# 07-SNESDRONE_Direct_IO_CART.net
KiCad netlist of a schematic drawn in Altium Designer
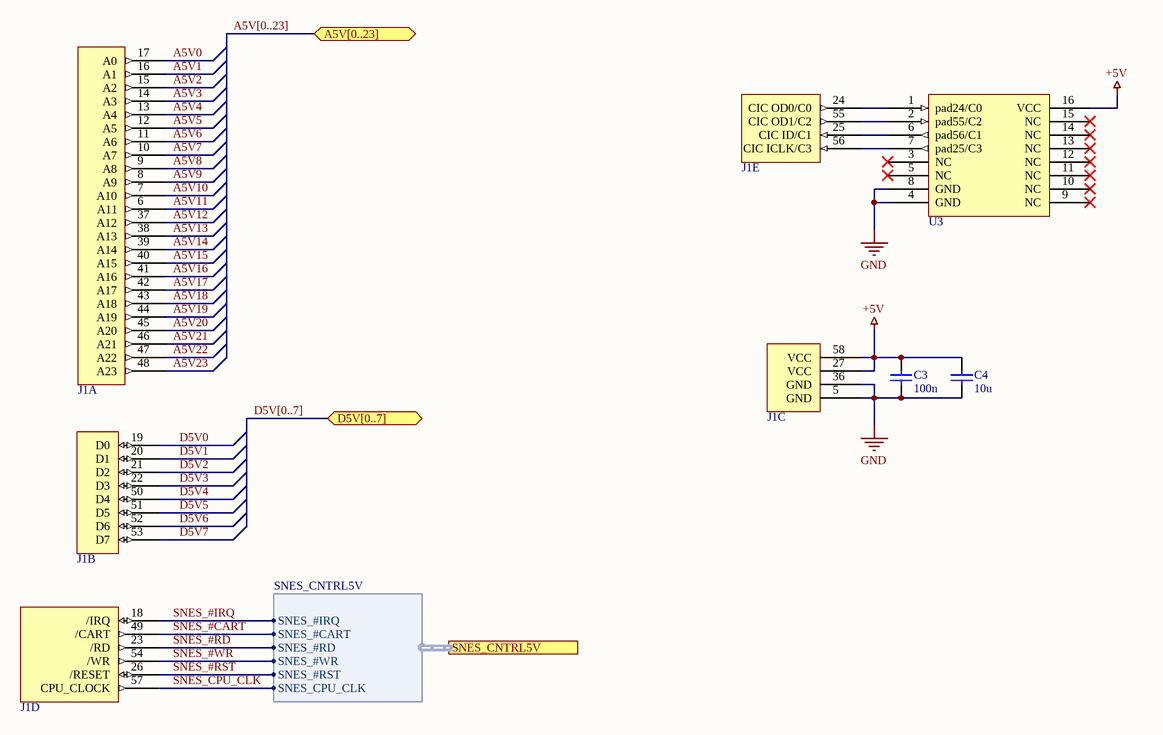
[diagram p0: 07-SNESDRONE_Direct_IO_CART.SchDoc]

(export (version "E")
  (design (tool "Eeschema 10.0.6"))
  (components
    (comp (ref "C3")
      (value "100n")
      (footprint "cap_0603")
      (description "Capacitor")
      (fields (field (name "Comment") "cap_0603"))
      (libsource (lib "mycomponents") (part "cap_0603"))
    )
    (comp (ref "C4")
      (value "10u")
      (footprint "cap_0603")
      (description "Capacitor")
      (fields (field (name "Comment") "cap_0603"))
      (libsource (lib "mycomponents") (part "cap_0603"))
    )
    (comp (ref "J1")
      (value "SNES Cartridge Connector")
      (footprint "SNES Cartridge Connector")
      (libsource (lib "") (part "SNES Cartridge Connector_1"))
    )
    (comp (ref "U3")
      (value "IC_D411A")
      (footprint "DIP16")
      (description "SNES CIC Chip")
      (libsource (lib "mycomponents") (part "IC_D411A"))
    )
  )
  (nets
    (net (code "2") (name "+5V") (class "Default")
      (node (ref "C3") (pin "2") (pinfunction "2_2") (pintype "passive"))
      (node (ref "C4") (pin "2") (pinfunction "2_2") (pintype "passive"))
      (node (ref "J1") (pin "27") (pinfunction "VCC_27") (pintype "power_in"))
      (node (ref "J1") (pin "58") (pinfunction "VCC_58") (pintype "power_in"))
      (node (ref "U3") (pin "16") (pinfunction "VCC_16") (pintype "power_in"))
    )
    (net (code "3") (name "/A5V0") (class "Default")
      (node (ref "J1") (pin "17") (pinfunction "A0_17") (pintype "output"))
    )
    (net (code "4") (name "/A5V1") (class "Default")
      (node (ref "J1") (pin "16") (pinfunction "A1_16") (pintype "output"))
    )
    (net (code "5") (name "/A5V2") (class "Default")
      (node (ref "J1") (pin "15") (pinfunction "A2_15") (pintype "output"))
    )
    (net (code "6") (name "/A5V3") (class "Default")
      (node (ref "J1") (pin "14") (pinfunction "A3_14") (pintype "output"))
    )
    (net (code "7") (name "/A5V4") (class "Default")
      (node (ref "J1") (pin "13") (pinfunction "A4_13") (pintype "output"))
    )
    (net (code "8") (name "/A5V5") (class "Default")
      (node (ref "J1") (pin "12") (pinfunction "A5_12") (pintype "output"))
    )
    (net (code "9") (name "/A5V6") (class "Default")
      (node (ref "J1") (pin "11") (pinfunction "A6_11") (pintype "output"))
    )
    (net (code "10") (name "/A5V7") (class "Default")
      (node (ref "J1") (pin "10") (pinfunction "A7_10") (pintype "output"))
    )
    (net (code "11") (name "/A5V8") (class "Default")
      (node (ref "J1") (pin "9") (pinfunction "A8_9") (pintype "output"))
    )
    (net (code "12") (name "/A5V9") (class "Default")
      (node (ref "J1") (pin "8") (pinfunction "A9_8") (pintype "output"))
    )
    (net (code "13") (name "/A5V10") (class "Default")
      (node (ref "J1") (pin "7") (pinfunction "A10_7") (pintype "output"))
    )
    (net (code "14") (name "/A5V11") (class "Default")
      (node (ref "J1") (pin "6") (pinfunction "A11_6") (pintype "output"))
    )
    (net (code "15") (name "/A5V12") (class "Default")
      (node (ref "J1") (pin "37") (pinfunction "A12_37") (pintype "output"))
    )
    (net (code "16") (name "/A5V13") (class "Default")
      (node (ref "J1") (pin "38") (pinfunction "A13_38") (pintype "output"))
    )
    (net (code "17") (name "/A5V14") (class "Default")
      (node (ref "J1") (pin "39") (pinfunction "A14_39") (pintype "output"))
    )
    (net (code "18") (name "/A5V15") (class "Default")
      (node (ref "J1") (pin "40") (pinfunction "A15_40") (pintype "output"))
    )
    (net (code "19") (name "/A5V16") (class "Default")
      (node (ref "J1") (pin "41") (pinfunction "A16_41") (pintype "output"))
    )
    (net (code "20") (name "/A5V17") (class "Default")
      (node (ref "J1") (pin "42") (pinfunction "A17_42") (pintype "output"))
    )
    (net (code "21") (name "/A5V18") (class "Default")
      (node (ref "J1") (pin "43") (pinfunction "A18_43") (pintype "output"))
    )
    (net (code "22") (name "/A5V19") (class "Default")
      (node (ref "J1") (pin "44") (pinfunction "A19_44") (pintype "output"))
    )
    (net (code "23") (name "/A5V20") (class "Default")
      (node (ref "J1") (pin "45") (pinfunction "A20_45") (pintype "output"))
    )
    (net (code "24") (name "/A5V21") (class "Default")
      (node (ref "J1") (pin "46") (pinfunction "A21_46") (pintype "output"))
    )
    (net (code "25") (name "/A5V22") (class "Default")
      (node (ref "J1") (pin "47") (pinfunction "A22_47") (pintype "output"))
    )
    (net (code "26") (name "/A5V23") (class "Default")
      (node (ref "J1") (pin "48") (pinfunction "A23_48") (pintype "output"))
    )
    (net (code "28") (name "/D5V0") (class "Default")
      (node (ref "J1") (pin "19") (pinfunction "D0_19") (pintype "bidirectional"))
    )
    (net (code "29") (name "/D5V1") (class "Default")
      (node (ref "J1") (pin "20") (pinfunction "D1_20") (pintype "bidirectional"))
    )
    (net (code "30") (name "/D5V2") (class "Default")
      (node (ref "J1") (pin "21") (pinfunction "D2_21") (pintype "bidirectional"))
    )
    (net (code "31") (name "/D5V3") (class "Default")
      (node (ref "J1") (pin "22") (pinfunction "D3_22") (pintype "bidirectional"))
    )
    (net (code "32") (name "/D5V4") (class "Default")
      (node (ref "J1") (pin "50") (pinfunction "D4_50") (pintype "bidirectional"))
    )
    (net (code "33") (name "/D5V5") (class "Default")
      (node (ref "J1") (pin "51") (pinfunction "D5_51") (pintype "bidirectional"))
    )
    (net (code "34") (name "/D5V6") (class "Default")
      (node (ref "J1") (pin "52") (pinfunction "D6_52") (pintype "bidirectional"))
    )
    (net (code "35") (name "/D5V7") (class "Default")
      (node (ref "J1") (pin "53") (pinfunction "D7_53") (pintype "bidirectional"))
    )
    (net (code "37") (name "/SNES_#CART") (class "Default")
      (node (ref "J1") (pin "49") (pinfunction "/CART_49") (pintype "output"))
    )
    (net (code "38") (name "/SNES_#IRQ") (class "Default")
      (node (ref "J1") (pin "18") (pinfunction "/IRQ_18") (pintype "bidirectional"))
    )
    (net (code "39") (name "/SNES_#RD") (class "Default")
      (node (ref "J1") (pin "23") (pinfunction "/RD_23") (pintype "output"))
    )
    (net (code "40") (name "/SNES_#RST") (class "Default")
      (node (ref "J1") (pin "26") (pinfunction "/RESET_26") (pintype "bidirectional"))
    )
    (net (code "41") (name "/SNES_#WR") (class "Default")
      (node (ref "J1") (pin "54") (pinfunction "/WR_54") (pintype "output"))
    )
    (net (code "42") (name "/SNES_CPU_CLK") (class "Default")
      (node (ref "J1") (pin "57") (pinfunction "CPU_CLOCK_57") (pintype "output"))
    )
    (net (code "44") (name "GND") (class "Default")
      (node (ref "C3") (pin "1") (pinfunction "1_1") (pintype "passive"))
      (node (ref "C4") (pin "1") (pinfunction "1_1") (pintype "passive"))
      (node (ref "J1") (pin "36") (pinfunction "GND_36") (pintype "power_in"))
      (node (ref "J1") (pin "5") (pinfunction "GND_5") (pintype "power_in"))
      (node (ref "U3") (pin "4") (pinfunction "GND_4") (pintype "power_in"))
      (node (ref "U3") (pin "8") (pinfunction "GND_8") (pintype "power_in"))
    )
    (net (code "45") (name "Net-(J1E-CIC_ICLK{slash}C3)") (class "Default")
      (node (ref "J1") (pin "56") (pinfunction "CIC_ICLK/C3_56") (pintype "input"))
      (node (ref "U3") (pin "7") (pinfunction "pad25/C3_7") (pintype "output"))
    )
    (net (code "46") (name "Net-(J1E-CIC_ID{slash}C1)") (class "Default")
      (node (ref "J1") (pin "25") (pinfunction "CIC_ID/C1_25") (pintype "input"))
      (node (ref "U3") (pin "6") (pinfunction "pad56/C1_6") (pintype "output"))
    )
    (net (code "47") (name "Net-(J1E-CIC_OD0{slash}C0)") (class "Default")
      (node (ref "J1") (pin "24") (pinfunction "CIC_OD0/C0_24") (pintype "output"))
      (node (ref "U3") (pin "1") (pinfunction "pad24/C0_1") (pintype "input"))
    )
    (net (code "48") (name "Net-(J1E-CIC_OD1{slash}C2)") (class "Default")
      (node (ref "J1") (pin "55") (pinfunction "CIC_OD1/C2_55") (pintype "output"))
      (node (ref "U3") (pin "2") (pinfunction "pad55/C2_2") (pintype "input"))
    )
    (net (code "49") (name "unconnected-(U3-NC-Pad3)") (class "Default")
      (node (ref "U3") (pin "3") (pinfunction "NC_3") (pintype "power_in+no_connect"))
    )
    (net (code "50") (name "unconnected-(U3-NC-Pad5)") (class "Default")
      (node (ref "U3") (pin "5") (pinfunction "NC_5") (pintype "power_in+no_connect"))
    )
    (net (code "51") (name "unconnected-(U3-NC-Pad9)") (class "Default")
      (node (ref "U3") (pin "9") (pinfunction "NC_9") (pintype "power_in+no_connect"))
    )
    (net (code "52") (name "unconnected-(U3-NC-Pad10)") (class "Default")
      (node (ref "U3") (pin "10") (pinfunction "NC_10") (pintype "power_in+no_connect"))
    )
    (net (code "53") (name "unconnected-(U3-NC-Pad11)") (class "Default")
      (node (ref "U3") (pin "11") (pinfunction "NC_11") (pintype "power_in+no_connect"))
    )
    (net (code "54") (name "unconnected-(U3-NC-Pad12)") (class "Default")
      (node (ref "U3") (pin "12") (pinfunction "NC_12") (pintype "power_in+no_connect"))
    )
    (net (code "55") (name "unconnected-(U3-NC-Pad13)") (class "Default")
      (node (ref "U3") (pin "13") (pinfunction "NC_13") (pintype "power_in+no_connect"))
    )
    (net (code "56") (name "unconnected-(U3-NC-Pad14)") (class "Default")
      (node (ref "U3") (pin "14") (pinfunction "NC_14") (pintype "power_in+no_connect"))
    )
    (net (code "57") (name "unconnected-(U3-NC-Pad15)") (class "Default")
      (node (ref "U3") (pin "15") (pinfunction "NC_15") (pintype "power_in+no_connect"))
    )
  )
)
